# SMT_Nixie_Board_HV5623.net
KiCad netlist of a schematic drawn in EAGLE
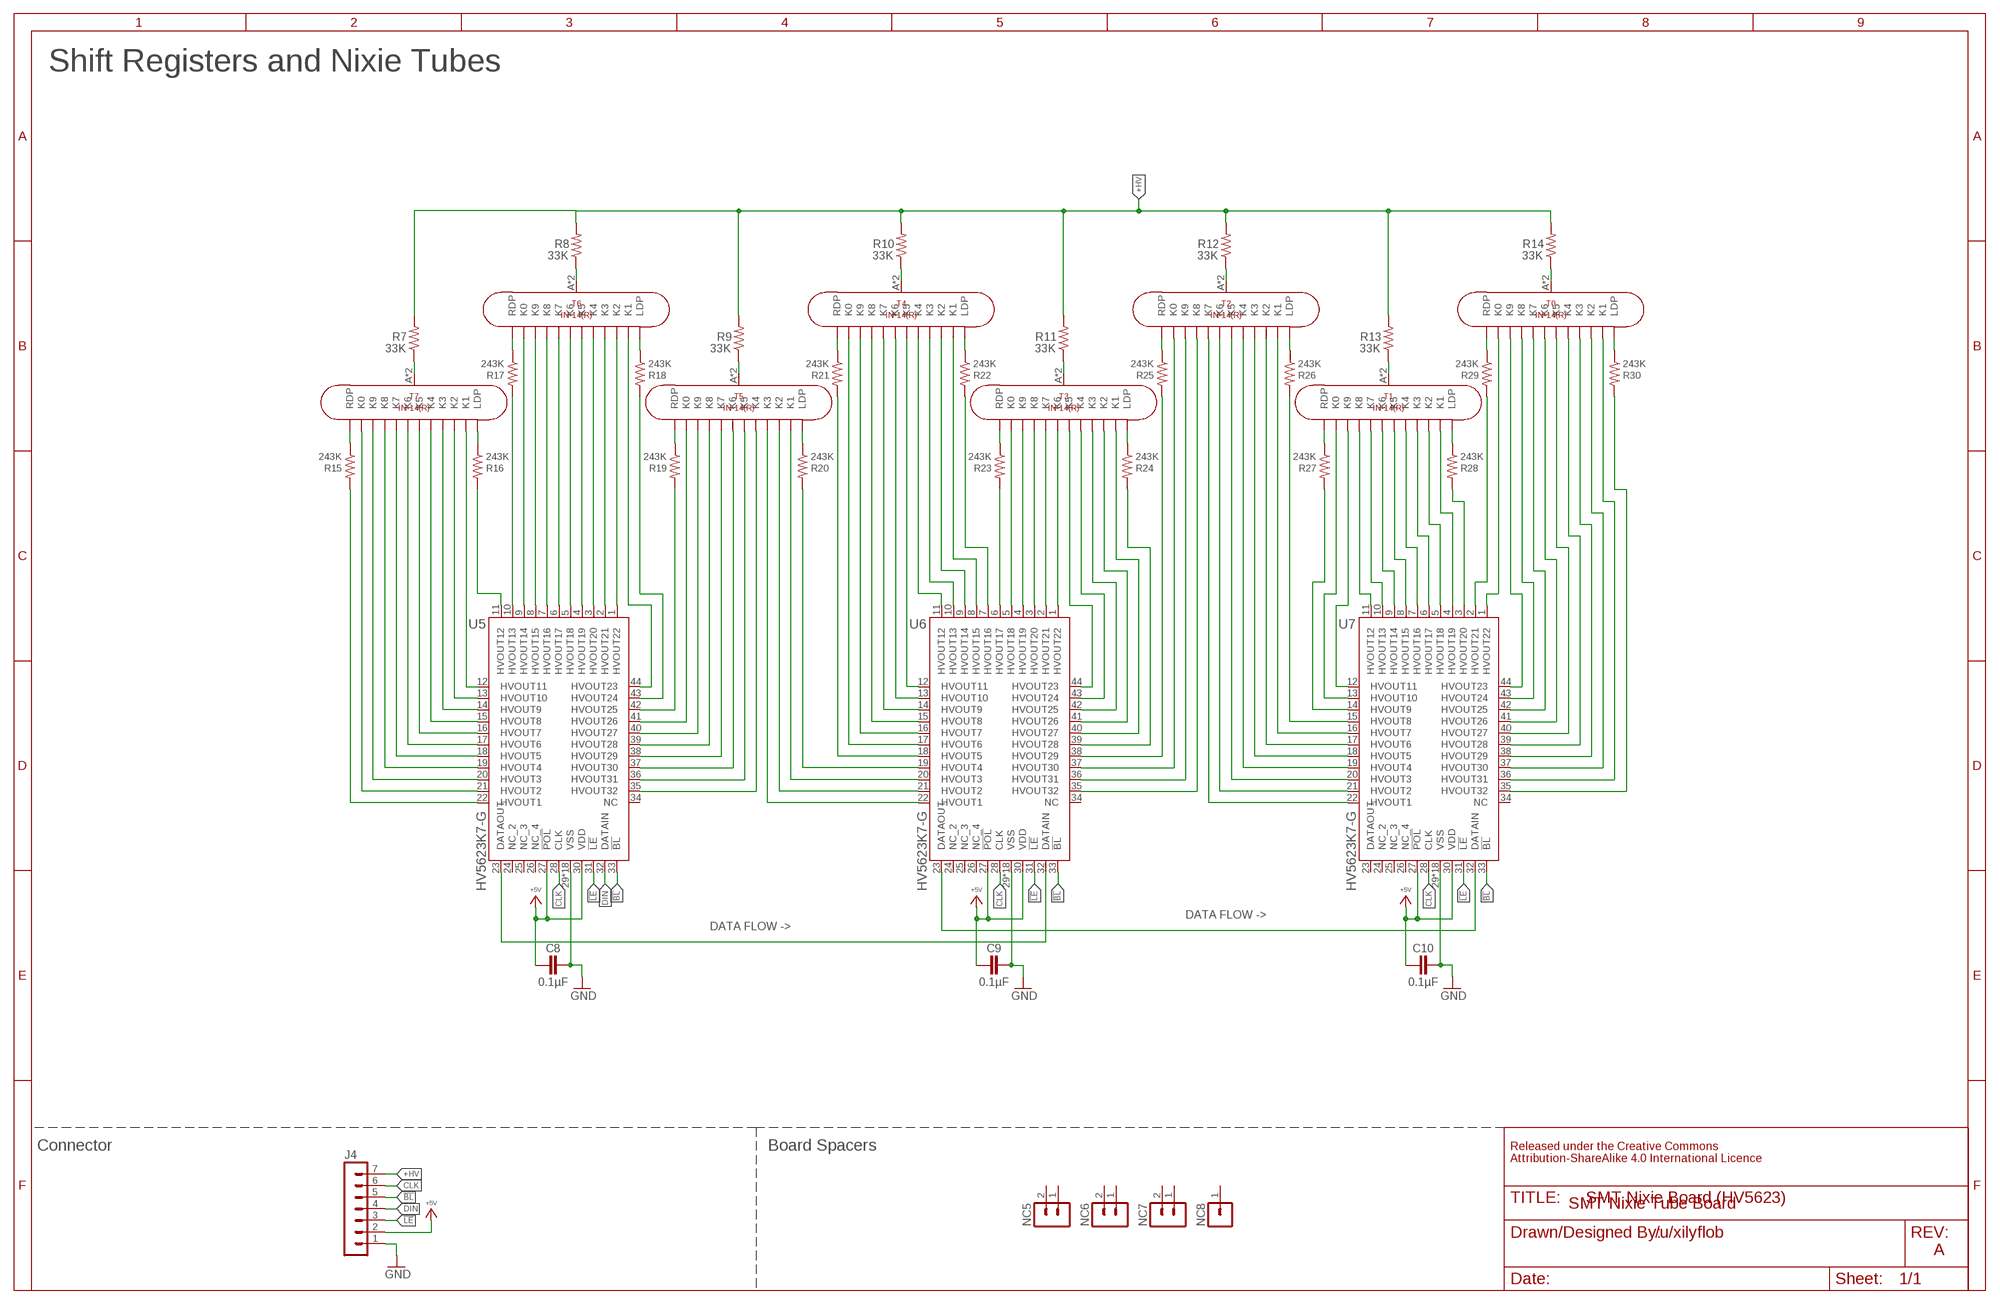
[diagram p0: schematic, sheet 1]

(export (version "E")
  (design (tool "Eeschema 10.0.6"))
  (components
    (comp (ref "C8")
      (value "0.1µF")
      (footprint "eagle-import:C0805")
      (libsource (lib "eagle-import") (part "C-EU"))
    )
    (comp (ref "C9")
      (value "0.1µF")
      (footprint "eagle-import:C0805")
      (libsource (lib "eagle-import") (part "C-EU"))
    )
    (comp (ref "C10")
      (value "0.1µF")
      (footprint "eagle-import:C0805")
      (libsource (lib "eagle-import") (part "C-EU"))
    )
    (comp (ref "J4")
      (value "1")
      (footprint "eagle-import:MA07")
      (libsource (lib "eagle-import") (part "MA07"))
    )
    (comp (ref "NC5")
      (value "MA02")
      (footprint "eagle-import:MA02")
      (libsource (lib "eagle-import") (part "MA02"))
    )
    (comp (ref "NC6")
      (value "MA02")
      (footprint "eagle-import:MA02")
      (libsource (lib "eagle-import") (part "MA02"))
    )
    (comp (ref "NC7")
      (value "MA02")
      (footprint "eagle-import:MA02")
      (libsource (lib "eagle-import") (part "MA02"))
    )
    (comp (ref "NC8")
      (value "MA01")
      (footprint "eagle-import:MA01")
      (libsource (lib "eagle-import") (part "MA01"))
    )
    (comp (ref "R7")
      (value "33K")
      (footprint "eagle-import:R2512")
      (libsource (lib "eagle-import") (part "R-US_R2512"))
    )
    (comp (ref "R8")
      (value "33K")
      (footprint "eagle-import:R2512")
      (libsource (lib "eagle-import") (part "R-US_R2512"))
    )
    (comp (ref "R9")
      (value "33K")
      (footprint "eagle-import:R2512")
      (libsource (lib "eagle-import") (part "R-US_R2512"))
    )
    (comp (ref "R10")
      (value "33K")
      (footprint "eagle-import:R2512")
      (libsource (lib "eagle-import") (part "R-US_R2512"))
    )
    (comp (ref "R11")
      (value "33K")
      (footprint "eagle-import:R2512")
      (libsource (lib "eagle-import") (part "R-US_R2512"))
    )
    (comp (ref "R12")
      (value "33K")
      (footprint "eagle-import:R2512")
      (libsource (lib "eagle-import") (part "R-US_R2512"))
    )
    (comp (ref "R13")
      (value "33K")
      (footprint "eagle-import:R2512")
      (libsource (lib "eagle-import") (part "R-US_R2512"))
    )
    (comp (ref "R14")
      (value "33K")
      (footprint "eagle-import:R2512")
      (libsource (lib "eagle-import") (part "R-US_R2512"))
    )
    (comp (ref "R15")
      (value "243K")
      (footprint "eagle-import:R2010")
      (libsource (lib "eagle-import") (part "R-US_R2010"))
    )
    (comp (ref "R16")
      (value "243K")
      (footprint "eagle-import:R2010")
      (libsource (lib "eagle-import") (part "R-US_R2010"))
    )
    (comp (ref "R17")
      (value "243K")
      (footprint "eagle-import:R2010")
      (libsource (lib "eagle-import") (part "R-US_R2010"))
    )
    (comp (ref "R18")
      (value "243K")
      (footprint "eagle-import:R2010")
      (libsource (lib "eagle-import") (part "R-US_R2010"))
    )
    (comp (ref "R19")
      (value "243K")
      (footprint "eagle-import:R2010")
      (libsource (lib "eagle-import") (part "R-US_R2010"))
    )
    (comp (ref "R20")
      (value "243K")
      (footprint "eagle-import:R2010")
      (libsource (lib "eagle-import") (part "R-US_R2010"))
    )
    (comp (ref "R21")
      (value "243K")
      (footprint "eagle-import:R2010")
      (libsource (lib "eagle-import") (part "R-US_R2010"))
    )
    (comp (ref "R22")
      (value "243K")
      (footprint "eagle-import:R2010")
      (libsource (lib "eagle-import") (part "R-US_R2010"))
    )
    (comp (ref "R23")
      (value "243K")
      (footprint "eagle-import:R2010")
      (libsource (lib "eagle-import") (part "R-US_R2010"))
    )
    (comp (ref "R24")
      (value "243K")
      (footprint "eagle-import:R2010")
      (libsource (lib "eagle-import") (part "R-US_R2010"))
    )
    (comp (ref "R25")
      (value "243K")
      (footprint "eagle-import:R2010")
      (libsource (lib "eagle-import") (part "R-US_R2010"))
    )
    (comp (ref "R26")
      (value "243K")
      (footprint "eagle-import:R2010")
      (libsource (lib "eagle-import") (part "R-US_R2010"))
    )
    (comp (ref "R27")
      (value "243K")
      (footprint "eagle-import:R2010")
      (libsource (lib "eagle-import") (part "R-US_R2010"))
    )
    (comp (ref "R28")
      (value "243K")
      (footprint "eagle-import:R2010")
      (libsource (lib "eagle-import") (part "R-US_R2010"))
    )
    (comp (ref "R29")
      (value "243K")
      (footprint "eagle-import:R2010")
      (libsource (lib "eagle-import") (part "R-US_R2010"))
    )
    (comp (ref "R30")
      (value "243K")
      (footprint "eagle-import:R2010")
      (libsource (lib "eagle-import") (part "R-US_R2010"))
    )
    (comp (ref "T0")
      (value "IN-14(R)")
      (footprint "eagle-import:IN-14_REVERSE")
      (libsource (lib "eagle-import") (part "IN-14(R)"))
    )
    (comp (ref "T1")
      (value "IN-14(R)")
      (footprint "eagle-import:IN-14_REVERSE")
      (libsource (lib "eagle-import") (part "IN-14(R)"))
    )
    (comp (ref "T2")
      (value "IN-14(R)")
      (footprint "eagle-import:IN-14_REVERSE")
      (libsource (lib "eagle-import") (part "IN-14(R)"))
    )
    (comp (ref "T3")
      (value "IN-14(R)")
      (footprint "eagle-import:IN-14_REVERSE")
      (libsource (lib "eagle-import") (part "IN-14(R)"))
    )
    (comp (ref "T4")
      (value "IN-14(R)")
      (footprint "eagle-import:IN-14_REVERSE")
      (libsource (lib "eagle-import") (part "IN-14(R)"))
    )
    (comp (ref "T5")
      (value "IN-14(R)")
      (footprint "eagle-import:IN-14_REVERSE")
      (libsource (lib "eagle-import") (part "IN-14(R)"))
    )
    (comp (ref "T6")
      (value "IN-14(R)")
      (footprint "eagle-import:IN-14_REVERSE")
      (libsource (lib "eagle-import") (part "IN-14(R)"))
    )
    (comp (ref "T7")
      (value "IN-14(R)")
      (footprint "eagle-import:IN-14_REVERSE")
      (libsource (lib "eagle-import") (part "IN-14(R)"))
    )
    (comp (ref "U5")
      (value "HV5623K7-G")
      (footprint "eagle-import:WQFN-44")
      (libsource (lib "eagle-import") (part "HV5623K7-G"))
    )
    (comp (ref "U6")
      (value "HV5623K7-G")
      (footprint "eagle-import:WQFN-44")
      (libsource (lib "eagle-import") (part "HV5623K7-G"))
    )
    (comp (ref "U7")
      (value "HV5623K7-G")
      (footprint "eagle-import:WQFN-44")
      (libsource (lib "eagle-import") (part "HV5623K7-G"))
    )
  )
  (nets
    (net (code "1") (name "+5V") (class "Default")
      (node (ref "C10") (pin "1") (pinfunction "1_1") (pintype "passive"))
      (node (ref "C8") (pin "1") (pinfunction "1_1") (pintype "passive"))
      (node (ref "C9") (pin "1") (pinfunction "1_1") (pintype "passive"))
      (node (ref "J4") (pin "2") (pinfunction "2_2") (pintype "passive"))
      (node (ref "U5") (pin "27") (pinfunction "~{POL}_27") (pintype "passive"))
      (node (ref "U5") (pin "30") (pinfunction "VDD_30") (pintype "power_in"))
      (node (ref "U6") (pin "27") (pinfunction "~{POL}_27") (pintype "passive"))
      (node (ref "U6") (pin "30") (pinfunction "VDD_30") (pintype "power_in"))
      (node (ref "U7") (pin "27") (pinfunction "~{POL}_27") (pintype "passive"))
      (node (ref "U7") (pin "30") (pinfunction "VDD_30") (pintype "power_in"))
    )
    (net (code "2") (name "+HV") (class "Default")
      (node (ref "J4") (pin "7") (pinfunction "7_7") (pintype "passive"))
      (node (ref "R10") (pin "2") (pinfunction "2_2") (pintype "passive"))
      (node (ref "R11") (pin "2") (pinfunction "2_2") (pintype "passive"))
      (node (ref "R12") (pin "2") (pinfunction "2_2") (pintype "passive"))
      (node (ref "R13") (pin "2") (pinfunction "2_2") (pintype "passive"))
      (node (ref "R14") (pin "2") (pinfunction "2_2") (pintype "passive"))
      (node (ref "R7") (pin "2") (pinfunction "2_2") (pintype "passive"))
      (node (ref "R8") (pin "2") (pinfunction "2_2") (pintype "passive"))
      (node (ref "R9") (pin "2") (pinfunction "2_2") (pintype "passive"))
    )
    (net (code "3") (name "/~{BL}") (class "Default")
      (node (ref "J4") (pin "5") (pinfunction "5_5") (pintype "passive"))
      (node (ref "U5") (pin "33") (pinfunction "~{BL}_33") (pintype "passive"))
      (node (ref "U6") (pin "33") (pinfunction "~{BL}_33") (pintype "passive"))
      (node (ref "U7") (pin "33") (pinfunction "~{BL}_33") (pintype "passive"))
    )
    (net (code "4") (name "/~{LE}") (class "Default")
      (node (ref "J4") (pin "3") (pinfunction "3_3") (pintype "passive"))
      (node (ref "U5") (pin "31") (pinfunction "~{LE}_31") (pintype "input"))
      (node (ref "U6") (pin "31") (pinfunction "~{LE}_31") (pintype "input"))
      (node (ref "U7") (pin "31") (pinfunction "~{LE}_31") (pintype "input"))
    )
    (net (code "5") (name "CLK") (class "Default")
      (node (ref "J4") (pin "6") (pinfunction "6_6") (pintype "passive"))
      (node (ref "U5") (pin "28") (pinfunction "CLK_28") (pintype "input"))
      (node (ref "U6") (pin "28") (pinfunction "CLK_28") (pintype "input"))
      (node (ref "U7") (pin "28") (pinfunction "CLK_28") (pintype "input"))
    )
    (net (code "6") (name "DIN") (class "Default")
      (node (ref "J4") (pin "4") (pinfunction "4_4") (pintype "passive"))
      (node (ref "U5") (pin "32") (pinfunction "DATAIN_32") (pintype "input"))
    )
    (net (code "7") (name "GND") (class "Default")
      (node (ref "C10") (pin "2") (pinfunction "2_2") (pintype "passive"))
      (node (ref "C8") (pin "2") (pinfunction "2_2") (pintype "passive"))
      (node (ref "C9") (pin "2") (pinfunction "2_2") (pintype "passive"))
      (node (ref "J4") (pin "1") (pinfunction "1_1") (pintype "passive"))
      (node (ref "U5") (pin "29") (pinfunction "VSS_29") (pintype "power_in"))
      (node (ref "U5") (pin "P$1") (pinfunction "VSS_P$1") (pintype "power_in"))
      (node (ref "U5") (pin "P$10") (pinfunction "VSS_P$10") (pintype "power_in"))
      (node (ref "U5") (pin "P$11") (pinfunction "VSS_P$11") (pintype "power_in"))
      (node (ref "U5") (pin "P$12") (pinfunction "VSS_P$12") (pintype "power_in"))
      (node (ref "U5") (pin "P$13") (pinfunction "VSS_P$13") (pintype "power_in"))
      (node (ref "U5") (pin "P$14") (pinfunction "VSS_P$14") (pintype "power_in"))
      (node (ref "U5") (pin "P$15") (pinfunction "VSS_P$15") (pintype "power_in"))
      (node (ref "U5") (pin "P$16") (pinfunction "VSS_P$16") (pintype "power_in"))
      (node (ref "U5") (pin "P$2") (pinfunction "VSS_P$2") (pintype "power_in"))
      (node (ref "U5") (pin "P$3") (pinfunction "VSS_P$3") (pintype "power_in"))
      (node (ref "U5") (pin "P$4") (pinfunction "VSS_P$4") (pintype "power_in"))
      (node (ref "U5") (pin "P$5") (pinfunction "VSS_P$5") (pintype "power_in"))
      (node (ref "U5") (pin "P$6") (pinfunction "VSS_P$6") (pintype "power_in"))
      (node (ref "U5") (pin "P$7") (pinfunction "VSS_P$7") (pintype "power_in"))
      (node (ref "U5") (pin "P$8") (pinfunction "VSS_P$8") (pintype "power_in"))
      (node (ref "U5") (pin "P$9") (pinfunction "VSS_P$9") (pintype "power_in"))
      (node (ref "U5") (pin "TP") (pinfunction "VSS_TP") (pintype "power_in"))
      (node (ref "U6") (pin "29") (pinfunction "VSS_29") (pintype "power_in"))
      (node (ref "U6") (pin "P$1") (pinfunction "VSS_P$1") (pintype "power_in"))
      (node (ref "U6") (pin "P$10") (pinfunction "VSS_P$10") (pintype "power_in"))
      (node (ref "U6") (pin "P$11") (pinfunction "VSS_P$11") (pintype "power_in"))
      (node (ref "U6") (pin "P$12") (pinfunction "VSS_P$12") (pintype "power_in"))
      (node (ref "U6") (pin "P$13") (pinfunction "VSS_P$13") (pintype "power_in"))
      (node (ref "U6") (pin "P$14") (pinfunction "VSS_P$14") (pintype "power_in"))
      (node (ref "U6") (pin "P$15") (pinfunction "VSS_P$15") (pintype "power_in"))
      (node (ref "U6") (pin "P$16") (pinfunction "VSS_P$16") (pintype "power_in"))
      (node (ref "U6") (pin "P$2") (pinfunction "VSS_P$2") (pintype "power_in"))
      (node (ref "U6") (pin "P$3") (pinfunction "VSS_P$3") (pintype "power_in"))
      (node (ref "U6") (pin "P$4") (pinfunction "VSS_P$4") (pintype "power_in"))
      (node (ref "U6") (pin "P$5") (pinfunction "VSS_P$5") (pintype "power_in"))
      (node (ref "U6") (pin "P$6") (pinfunction "VSS_P$6") (pintype "power_in"))
      (node (ref "U6") (pin "P$7") (pinfunction "VSS_P$7") (pintype "power_in"))
      (node (ref "U6") (pin "P$8") (pinfunction "VSS_P$8") (pintype "power_in"))
      (node (ref "U6") (pin "P$9") (pinfunction "VSS_P$9") (pintype "power_in"))
      (node (ref "U6") (pin "TP") (pinfunction "VSS_TP") (pintype "power_in"))
      (node (ref "U7") (pin "29") (pinfunction "VSS_29") (pintype "power_in"))
      (node (ref "U7") (pin "P$1") (pinfunction "VSS_P$1") (pintype "power_in"))
      (node (ref "U7") (pin "P$10") (pinfunction "VSS_P$10") (pintype "power_in"))
      (node (ref "U7") (pin "P$11") (pinfunction "VSS_P$11") (pintype "power_in"))
      (node (ref "U7") (pin "P$12") (pinfunction "VSS_P$12") (pintype "power_in"))
      (node (ref "U7") (pin "P$13") (pinfunction "VSS_P$13") (pintype "power_in"))
      (node (ref "U7") (pin "P$14") (pinfunction "VSS_P$14") (pintype "power_in"))
      (node (ref "U7") (pin "P$15") (pinfunction "VSS_P$15") (pintype "power_in"))
      (node (ref "U7") (pin "P$16") (pinfunction "VSS_P$16") (pintype "power_in"))
      (node (ref "U7") (pin "P$2") (pinfunction "VSS_P$2") (pintype "power_in"))
      (node (ref "U7") (pin "P$3") (pinfunction "VSS_P$3") (pintype "power_in"))
      (node (ref "U7") (pin "P$4") (pinfunction "VSS_P$4") (pintype "power_in"))
      (node (ref "U7") (pin "P$5") (pinfunction "VSS_P$5") (pintype "power_in"))
      (node (ref "U7") (pin "P$6") (pinfunction "VSS_P$6") (pintype "power_in"))
      (node (ref "U7") (pin "P$7") (pinfunction "VSS_P$7") (pintype "power_in"))
      (node (ref "U7") (pin "P$8") (pinfunction "VSS_P$8") (pintype "power_in"))
      (node (ref "U7") (pin "P$9") (pinfunction "VSS_P$9") (pintype "power_in"))
      (node (ref "U7") (pin "TP") (pinfunction "VSS_TP") (pintype "power_in"))
    )
    (net (code "8") (name "Net-(R7-Pad1)") (class "Default")
      (node (ref "R7") (pin "1") (pinfunction "1_1") (pintype "passive"))
      (node (ref "T7") (pin "A") (pinfunction "A_A") (pintype "output"))
      (node (ref "T7") (pin "A_1") (pinfunction "A_A_1") (pintype "output"))
    )
    (net (code "9") (name "Net-(R8-Pad1)") (class "Default")
      (node (ref "R8") (pin "1") (pinfunction "1_1") (pintype "passive"))
      (node (ref "T6") (pin "A") (pinfunction "A_A") (pintype "output"))
      (node (ref "T6") (pin "A_1") (pinfunction "A_A_1") (pintype "output"))
    )
    (net (code "10") (name "Net-(R9-Pad1)") (class "Default")
      (node (ref "R9") (pin "1") (pinfunction "1_1") (pintype "passive"))
      (node (ref "T5") (pin "A") (pinfunction "A_A") (pintype "output"))
      (node (ref "T5") (pin "A_1") (pinfunction "A_A_1") (pintype "output"))
    )
    (net (code "11") (name "Net-(R10-Pad1)") (class "Default")
      (node (ref "R10") (pin "1") (pinfunction "1_1") (pintype "passive"))
      (node (ref "T4") (pin "A") (pinfunction "A_A") (pintype "output"))
      (node (ref "T4") (pin "A_1") (pinfunction "A_A_1") (pintype "output"))
    )
    (net (code "12") (name "Net-(R11-Pad1)") (class "Default")
      (node (ref "R11") (pin "1") (pinfunction "1_1") (pintype "passive"))
      (node (ref "T3") (pin "A") (pinfunction "A_A") (pintype "output"))
      (node (ref "T3") (pin "A_1") (pinfunction "A_A_1") (pintype "output"))
    )
    (net (code "13") (name "Net-(R12-Pad1)") (class "Default")
      (node (ref "R12") (pin "1") (pinfunction "1_1") (pintype "passive"))
      (node (ref "T2") (pin "A") (pinfunction "A_A") (pintype "output"))
      (node (ref "T2") (pin "A_1") (pinfunction "A_A_1") (pintype "output"))
    )
    (net (code "14") (name "Net-(R13-Pad1)") (class "Default")
      (node (ref "R13") (pin "1") (pinfunction "1_1") (pintype "passive"))
      (node (ref "T1") (pin "A") (pinfunction "A_A") (pintype "output"))
      (node (ref "T1") (pin "A_1") (pinfunction "A_A_1") (pintype "output"))
    )
    (net (code "15") (name "Net-(R14-Pad1)") (class "Default")
      (node (ref "R14") (pin "1") (pinfunction "1_1") (pintype "passive"))
      (node (ref "T0") (pin "A") (pinfunction "A_A") (pintype "output"))
      (node (ref "T0") (pin "A_1") (pinfunction "A_A_1") (pintype "output"))
    )
    (net (code "16") (name "Net-(R15-Pad1)") (class "Default")
      (node (ref "R15") (pin "1") (pinfunction "1_1") (pintype "passive"))
      (node (ref "T7") (pin "RDP") (pinfunction "RDP_RDP") (pintype "input"))
      (node (ref "T7") (pin "RDP_1") (pinfunction "RDP_RDP_1") (pintype "input"))
    )
    (net (code "17") (name "Net-(R16-Pad1)") (class "Default")
      (node (ref "R16") (pin "1") (pinfunction "1_1") (pintype "passive"))
      (node (ref "T7") (pin "LDP") (pinfunction "LDP_LDP") (pintype "input"))
      (node (ref "T7") (pin "LDP_1") (pinfunction "LDP_LDP_1") (pintype "input"))
    )
    (net (code "18") (name "Net-(R17-Pad1)") (class "Default")
      (node (ref "R17") (pin "1") (pinfunction "1_1") (pintype "passive"))
      (node (ref "T6") (pin "RDP") (pinfunction "RDP_RDP") (pintype "input"))
      (node (ref "T6") (pin "RDP_1") (pinfunction "RDP_RDP_1") (pintype "input"))
    )
    (net (code "19") (name "Net-(R18-Pad1)") (class "Default")
      (node (ref "R18") (pin "1") (pinfunction "1_1") (pintype "passive"))
      (node (ref "T6") (pin "LDP") (pinfunction "LDP_LDP") (pintype "input"))
      (node (ref "T6") (pin "LDP_1") (pinfunction "LDP_LDP_1") (pintype "input"))
    )
    (net (code "20") (name "Net-(R19-Pad1)") (class "Default")
      (node (ref "R19") (pin "1") (pinfunction "1_1") (pintype "passive"))
      (node (ref "T5") (pin "RDP") (pinfunction "RDP_RDP") (pintype "input"))
      (node (ref "T5") (pin "RDP_1") (pinfunction "RDP_RDP_1") (pintype "input"))
    )
    (net (code "21") (name "Net-(R20-Pad1)") (class "Default")
      (node (ref "R20") (pin "1") (pinfunction "1_1") (pintype "passive"))
      (node (ref "T5") (pin "LDP") (pinfunction "LDP_LDP") (pintype "input"))
      (node (ref "T5") (pin "LDP_1") (pinfunction "LDP_LDP_1") (pintype "input"))
    )
    (net (code "22") (name "Net-(R21-Pad1)") (class "Default")
      (node (ref "R21") (pin "1") (pinfunction "1_1") (pintype "passive"))
      (node (ref "T4") (pin "RDP") (pinfunction "RDP_RDP") (pintype "input"))
      (node (ref "T4") (pin "RDP_1") (pinfunction "RDP_RDP_1") (pintype "input"))
    )
    (net (code "23") (name "Net-(R22-Pad1)") (class "Default")
      (node (ref "R22") (pin "1") (pinfunction "1_1") (pintype "passive"))
      (node (ref "T4") (pin "LDP") (pinfunction "LDP_LDP") (pintype "input"))
      (node (ref "T4") (pin "LDP_1") (pinfunction "LDP_LDP_1") (pintype "input"))
    )
    (net (code "24") (name "Net-(R23-Pad1)") (class "Default")
      (node (ref "R23") (pin "1") (pinfunction "1_1") (pintype "passive"))
      (node (ref "T3") (pin "RDP") (pinfunction "RDP_RDP") (pintype "input"))
      (node (ref "T3") (pin "RDP_1") (pinfunction "RDP_RDP_1") (pintype "input"))
    )
    (net (code "25") (name "Net-(R24-Pad1)") (class "Default")
      (node (ref "R24") (pin "1") (pinfunction "1_1") (pintype "passive"))
      (node (ref "T3") (pin "LDP") (pinfunction "LDP_LDP") (pintype "input"))
      (node (ref "T3") (pin "LDP_1") (pinfunction "LDP_LDP_1") (pintype "input"))
    )
    (net (code "26") (name "Net-(R25-Pad1)") (class "Default")
      (node (ref "R25") (pin "1") (pinfunction "1_1") (pintype "passive"))
      (node (ref "T2") (pin "RDP") (pinfunction "RDP_RDP") (pintype "input"))
      (node (ref "T2") (pin "RDP_1") (pinfunction "RDP_RDP_1") (pintype "input"))
    )
    (net (code "27") (name "Net-(R26-Pad1)") (class "Default")
      (node (ref "R26") (pin "1") (pinfunction "1_1") (pintype "passive"))
      (node (ref "T2") (pin "LDP") (pinfunction "LDP_LDP") (pintype "input"))
      (node (ref "T2") (pin "LDP_1") (pinfunction "LDP_LDP_1") (pintype "input"))
    )
    (net (code "28") (name "Net-(R27-Pad1)") (class "Default")
      (node (ref "R27") (pin "1") (pinfunction "1_1") (pintype "passive"))
      (node (ref "T1") (pin "RDP") (pinfunction "RDP_RDP") (pintype "input"))
      (node (ref "T1") (pin "RDP_1") (pinfunction "RDP_RDP_1") (pintype "input"))
    )
    (net (code "29") (name "Net-(R28-Pad1)") (class "Default")
      (node (ref "R28") (pin "1") (pinfunction "1_1") (pintype "passive"))
      (node (ref "T1") (pin "LDP") (pinfunction "LDP_LDP") (pintype "input"))
      (node (ref "T1") (pin "LDP_1") (pinfunction "LDP_LDP_1") (pintype "input"))
    )
    (net (code "30") (name "Net-(R29-Pad1)") (class "Default")
      (node (ref "R29") (pin "1") (pinfunction "1_1") (pintype "passive"))
      (node (ref "T0") (pin "RDP") (pinfunction "RDP_RDP") (pintype "input"))
      (node (ref "T0") (pin "RDP_1") (pinfunction "RDP_RDP_1") (pintype "input"))
    )
    (net (code "31") (name "Net-(R30-Pad1)") (class "Default")
      (node (ref "R30") (pin "1") (pinfunction "1_1") (pintype "passive"))
      (node (ref "T0") (pin "LDP") (pinfunction "LDP_LDP") (pintype "input"))
      (node (ref "T0") (pin "LDP_1") (pinfunction "LDP_LDP_1") (pintype "input"))
    )
    (net (code "32") (name "Net-(U5-DATAOUT)") (class "Default")
      (node (ref "U5") (pin "23") (pinfunction "DATAOUT_23") (pintype "output"))
      (node (ref "U6") (pin "32") (pinfunction "DATAIN_32") (pintype "input"))
    )
    (net (code "33") (name "Net-(U5-HVOUT1)") (class "Default")
      (node (ref "R15") (pin "2") (pinfunction "2_2") (pintype "passive"))
      (node (ref "U5") (pin "22") (pinfunction "HVOUT1_22") (pintype "output"))
    )
    (net (code "34") (name "Net-(U5-HVOUT2)") (class "Default")
      (node (ref "T7") (pin "K0") (pinfunction "K0_K0") (pintype "input"))
      (node (ref "T7") (pin "K0_1") (pinfunction "K0_K0_1") (pintype "input"))
      (node (ref "U5") (pin "21") (pinfunction "HVOUT2_21") (pintype "output"))
    )
    (net (code "35") (name "Net-(U5-HVOUT3)") (class "Default")
      (node (ref "T7") (pin "K9") (pinfunction "K9_K9") (pintype "input"))
      (node (ref "T7") (pin "K9_1") (pinfunction "K9_K9_1") (pintype "input"))
      (node (ref "U5") (pin "20") (pinfunction "HVOUT3_20") (pintype "output"))
    )
    (net (code "36") (name "Net-(U5-HVOUT4)") (class "Default")
      (node (ref "T7") (pin "K8") (pinfunction "K8_K8") (pintype "input"))
      (node (ref "T7") (pin "K8_1") (pinfunction "K8_K8_1") (pintype "input"))
      (node (ref "U5") (pin "19") (pinfunction "HVOUT4_19") (pintype "output"))
    )
    (net (code "37") (name "Net-(U5-HVOUT5)") (class "Default")
      (node (ref "T7") (pin "K7") (pinfunction "K7_K7") (pintype "input"))
      (node (ref "T7") (pin "K7_1") (pinfunction "K7_K7_1") (pintype "input"))
      (node (ref "U5") (pin "18") (pinfunction "HVOUT5_18") (pintype "output"))
    )
    (net (code "38") (name "Net-(U5-HVOUT6)") (class "Default")
      (node (ref "T7") (pin "K6") (pinfunction "K6_K6") (pintype "input"))
      (node (ref "T7") (pin "K6_1") (pinfunction "K6_K6_1") (pintype "input"))
      (node (ref "U5") (pin "17") (pinfunction "HVOUT6_17") (pintype "output"))
    )
    (net (code "39") (name "Net-(U5-HVOUT7)") (class "Default")
      (node (ref "T7") (pin "K5") (pinfunction "K5_K5") (pintype "input"))
      (node (ref "T7") (pin "K5_1") (pinfunction "K5_K5_1") (pintype "input"))
      (node (ref "U5") (pin "16") (pinfunction "HVOUT7_16") (pintype "output"))
    )
    (net (code "40") (name "Net-(U5-HVOUT8)") (class "Default")
      (node (ref "T7") (pin "K4") (pinfunction "K4_K4") (pintype "input"))
      (node (ref "T7") (pin "K4_1") (pinfunction "K4_K4_1") (pintype "input"))
      (node (ref "U5") (pin "15") (pinfunction "HVOUT8_15") (pintype "output"))
    )
    (net (code "41") (name "Net-(U5-HVOUT9)") (class "Default")
      (node (ref "T7") (pin "K3") (pinfunction "K3_K3") (pintype "input"))
      (node (ref "T7") (pin "K3_1") (pinfunction "K3_K3_1") (pintype "input"))
      (node (ref "U5") (pin "14") (pinfunction "HVOUT9_14") (pintype "output"))
    )
    (net (code "42") (name "Net-(U5-HVOUT10)") (class "Default")
      (node (ref "T7") (pin "K2") (pinfunction "K2_K2") (pintype "input"))
      (node (ref "T7") (pin "K2_1") (pinfunction "K2_K2_1") (pintype "input"))
      (node (ref "U5") (pin "13") (pinfunction "HVOUT10_13") (pintype "output"))
    )
    (net (code "43") (name "Net-(U5-HVOUT11)") (class "Default")
      (node (ref "T7") (pin "K1") (pinfunction "K1_K1") (pintype "input"))
      (node (ref "T7") (pin "K1_1") (pinfunction "K1_K1_1") (pintype "input"))
      (node (ref "U5") (pin "12") (pinfunction "HVOUT11_12") (pintype "output"))
    )
    (net (code "44") (name "Net-(U5-HVOUT12)") (class "Default")
      (node (ref "R16") (pin "2") (pinfunction "2_2") (pintype "passive"))
      (node (ref "U5") (pin "11") (pinfunction "HVOUT12_11") (pintype "output"))
    )
    (net (code "45") (name "Net-(U5-HVOUT13)") (class "Default")
      (node (ref "R17") (pin "2") (pinfunction "2_2") (pintype "passive"))
      (node (ref "U5") (pin "10") (pinfunction "HVOUT13_10") (pintype "output"))
    )
    (net (code "46") (name "Net-(U5-HVOUT14)") (class "Default")
      (node (ref "T6") (pin "K0") (pinfunction "K0_K0") (pintype "input"))
      (node (ref "T6") (pin "K0_1") (pinfunction "K0_K0_1") (pintype "input"))
      (node (ref "U5") (pin "9") (pinfunction "HVOUT14_9") (pintype "output"))
    )
    (net (code "47") (name "Net-(U5-HVOUT15)") (class "Default")
      (node (ref "T6") (pin "K9") (pinfunction "K9_K9") (pintype "input"))
      (node (ref "T6") (pin "K9_1") (pinfunction "K9_K9_1") (pintype "input"))
      (node (ref "U5") (pin "8") (pinfunction "HVOUT15_8") (pintype "output"))
    )
    (net (code "48") (name "Net-(U5-HVOUT16)") (class "Default")
      (node (ref "T6") (pin "K8") (pinfunction "K8_K8") (pintype "input"))
      (node (ref "T6") (pin "K8_1") (pinfunction "K8_K8_1") (pintype "input"))
      (node (ref "U5") (pin "7") (pinfunction "HVOUT16_7") (pintype "output"))
    )
    (net (code "49") (name "Net-(U5-HVOUT17)") (class "Default")
      (node (ref "T6") (pin "K7") (pinfunction "K7_K7") (pintype "input"))
      (node (ref "T6") (pin "K7_1") (pinfunction "K7_K7_1") (pintype "input"))
      (node (ref "U5") (pin "6") (pinfunction "HVOUT17_6") (pintype "output"))
    )
    (net (code "50") (name "Net-(U5-HVOUT18)") (class "Default")
      (node (ref "T6") (pin "K6") (pinfunction "K6_K6") (pintype "input"))
      (node (ref "T6") (pin "K6_1") (pinfunction "K6_K6_1") (pintype "input"))
      (node (ref "U5") (pin "5") (pinfunction "HVOUT18_5") (pintype "output"))
    )
    (net (code "51") (name "Net-(U5-HVOUT19)") (class "Default")
      (node (ref "T6") (pin "K5") (pinfunction "K5_K5") (pintype "input"))
      (node (ref "T6") (pin "K5_1") (pinfunction "K5_K5_1") (pintype "input"))
      (node (ref "U5") (pin "4") (pinfunction "HVOUT19_4") (pintype "output"))
    )
    (net (code "52") (name "Net-(U5-HVOUT20)") (class "Default")
      (node (ref "T6") (pin "K4") (pinfunction "K4_K4") (pintype "input"))
      (node (ref "T6") (pin "K4_1") (pinfunction "K4_K4_1") (pintype "input"))
      (node (ref "U5") (pin "3") (pinfunction "HVOUT20_3") (pintype "output"))
    )
    (net (code "53") (name "Net-(U5-HVOUT21)") (class "Default")
      (node (ref "T6") (pin "K3") (pinfunction "K3_K3") (pintype "input"))
      (node (ref "T6") (pin "K3_1") (pinfunction "K3_K3_1") (pintype "input"))
      (node (ref "U5") (pin "2") (pinfunction "HVOUT21_2") (pintype "output"))
    )
    (net (code "54") (name "Net-(U5-HVOUT22)") (class "Default")
      (node (ref "T6") (pin "K2") (pinfunction "K2_K2") (pintype "input"))
      (node (ref "T6") (pin "K2_1") (pinfunction "K2_K2_1") (pintype "input"))
      (node (ref "U5") (pin "1") (pinfunction "HVOUT22_1") (pintype "output"))
    )
    (net (code "55") (name "Net-(U5-HVOUT23)") (class "Default")
      (node (ref "T6") (pin "K1") (pinfunction "K1_K1") (pintype "input"))
      (node (ref "T6") (pin "K1_1") (pinfunction "K1_K1_1") (pintype "input"))
      (node (ref "U5") (pin "44") (pinfunction "HVOUT23_44") (pintype "output"))
    )
    (net (code "56") (name "Net-(U5-HVOUT24)") (class "Default")
      (node (ref "R18") (pin "2") (pinfunction "2_2") (pintype "passive"))
      (node (ref "U5") (pin "43") (pinfunction "HVOUT24_43") (pintype "output"))
    )
    (net (code "57") (name "Net-(U5-HVOUT25)") (class "Default")
      (node (ref "R19") (pin "2") (pinfunction "2_2") (pintype "passive"))
      (node (ref "U5") (pin "42") (pinfunction "HVOUT25_42") (pintype "output"))
    )
    (net (code "58") (name "Net-(U5-HVOUT26)") (class "Default")
      (node (ref "T5") (pin "K0") (pinfunction "K0_K0") (pintype "input"))
      (node (ref "T5") (pin "K0_1") (pinfunction "K0_K0_1") (pintype "input"))
      (node (ref "U5") (pin "41") (pinfunction "HVOUT26_41") (pintype "output"))
    )
    (net (code "59") (name "Net-(U5-HVOUT27)") (class "Default")
      (node (ref "T5") (pin "K9") (pinfunction "K9_K9") (pintype "input"))
      (node (ref "T5") (pin "K9_1") (pinfunction "K9_K9_1") (pintype "input"))
      (node (ref "U5") (pin "40") (pinfunction "HVOUT27_40") (pintype "output"))
    )
    (net (code "60") (name "Net-(U5-HVOUT28)") (class "Default")
      (node (ref "T5") (pin "K8") (pinfunction "K8_K8") (pintype "input"))
      (node (ref "T5") (pin "K8_1") (pinfunction "K8_K8_1") (pintype "input"))
      (node (ref "U5") (pin "39") (pinfunction "HVOUT28_39") (pintype "output"))
    )
    (net (code "61") (name "Net-(U5-HVOUT29)") (class "Default")
      (node (ref "T5") (pin "K7") (pinfunction "K7_K7") (pintype "input"))
      (node (ref "T5") (pin "K7_1") (pinfunction "K7_K7_1") (pintype "input"))
      (node (ref "U5") (pin "38") (pinfunction "HVOUT29_38") (pintype "output"))
    )
    (net (code "62") (name "Net-(U5-HVOUT30)") (class "Default")
      (node (ref "T5") (pin "K6") (pinfunction "K6_K6") (pintype "input"))
      (node (ref "T5") (pin "K6_1") (pinfunction "K6_K6_1") (pintype "input"))
      (node (ref "U5") (pin "37") (pinfunction "HVOUT30_37") (pintype "output"))
    )
    (net (code "63") (name "Net-(U5-HVOUT31)") (class "Default")
      (node (ref "T5") (pin "K5") (pinfunction "K5_K5") (pintype "input"))
      (node (ref "T5") (pin "K5_1") (pinfunction "K5_K5_1") (pintype "input"))
      (node (ref "U5") (pin "36") (pinfunction "HVOUT31_36") (pintype "output"))
    )
    (net (code "64") (name "Net-(U5-HVOUT32)") (class "Default")
      (node (ref "T5") (pin "K4") (pinfunction "K4_K4") (pintype "input"))
      (node (ref "T5") (pin "K4_1") (pinfunction "K4_K4_1") (pintype "input"))
      (node (ref "U5") (pin "35") (pinfunction "HVOUT32_35") (pintype "output"))
    )
    (net (code "65") (name "Net-(U6-DATAOUT)") (class "Default")
      (node (ref "U6") (pin "23") (pinfunction "DATAOUT_23") (pintype "output"))
      (node (ref "U7") (pin "32") (pinfunction "DATAIN_32") (pintype "input"))
    )
    (net (code "66") (name "Net-(U6-HVOUT1)") (class "Default")
      (node (ref "T5") (pin "K3") (pinfunction "K3_K3") (pintype "input"))
      (node (ref "T5") (pin "K3_1") (pinfunction "K3_K3_1") (pintype "input"))
      (node (ref "U6") (pin "22") (pinfunction "HVOUT1_22") (pintype "output"))
    )
    (net (code "67") (name "Net-(U6-HVOUT2)") (class "Default")
      (node (ref "T5") (pin "K2") (pinfunction "K2_K2") (pintype "input"))
      (node (ref "T5") (pin "K2_1") (pinfunction "K2_K2_1") (pintype "input"))
      (node (ref "U6") (pin "21") (pinfunction "HVOUT2_21") (pintype "output"))
    )
    (net (code "68") (name "Net-(U6-HVOUT3)") (class "Default")
      (node (ref "T5") (pin "K1") (pinfunction "K1_K1") (pintype "input"))
      (node (ref "T5") (pin "K1_1") (pinfunction "K1_K1_1") (pintype "input"))
      (node (ref "U6") (pin "20") (pinfunction "HVOUT3_20") (pintype "output"))
    )
    (net (code "69") (name "Net-(U6-HVOUT4)") (class "Default")
      (node (ref "R20") (pin "2") (pinfunction "2_2") (pintype "passive"))
      (node (ref "U6") (pin "19") (pinfunction "HVOUT4_19") (pintype "output"))
    )
    (net (code "70") (name "Net-(U6-HVOUT5)") (class "Default")
      (node (ref "R21") (pin "2") (pinfunction "2_2") (pintype "passive"))
      (node (ref "U6") (pin "18") (pinfunction "HVOUT5_18") (pintype "output"))
    )
    (net (code "71") (name "Net-(U6-HVOUT6)") (class "Default")
      (node (ref "T4") (pin "K0") (pinfunction "K0_K0") (pintype "input"))
      (node (ref "T4") (pin "K0_1") (pinfunction "K0_K0_1") (pintype "input"))
      (node (ref "U6") (pin "17") (pinfunction "HVOUT6_17") (pintype "output"))
    )
    (net (code "72") (name "Net-(U6-HVOUT7)") (class "Default")
      (node (ref "T4") (pin "K9") (pinfunction "K9_K9") (pintype "input"))
      (node (ref "T4") (pin "K9_1") (pinfunction "K9_K9_1") (pintype "input"))
      (node (ref "U6") (pin "16") (pinfunction "HVOUT7_16") (pintype "output"))
    )
    (net (code "73") (name "Net-(U6-HVOUT8)") (class "Default")
      (node (ref "T4") (pin "K8") (pinfunction "K8_K8") (pintype "input"))
      (node (ref "T4") (pin "K8_1") (pinfunction "K8_K8_1") (pintype "input"))
      (node (ref "U6") (pin "15") (pinfunction "HVOUT8_15") (pintype "output"))
    )
    (net (code "74") (name "Net-(U6-HVOUT9)") (class "Default")
      (node (ref "T4") (pin "K7") (pinfunction "K7_K7") (pintype "input"))
      (node (ref "T4") (pin "K7_1") (pinfunction "K7_K7_1") (pintype "input"))
      (node (ref "U6") (pin "14") (pinfunction "HVOUT9_14") (pintype "output"))
    )
    (net (code "75") (name "Net-(U6-HVOUT10)") (class "Default")
      (node (ref "T4") (pin "K6") (pinfunction "K6_K6") (pintype "input"))
      (node (ref "T4") (pin "K6_1") (pinfunction "K6_K6_1") (pintype "input"))
      (node (ref "U6") (pin "13") (pinfunction "HVOUT10_13") (pintype "output"))
    )
    (net (code "76") (name "Net-(U6-HVOUT11)") (class "Default")
      (node (ref "T4") (pin "K5") (pinfunction "K5_K5") (pintype "input"))
      (node (ref "T4") (pin "K5_1") (pinfunction "K5_K5_1") (pintype "input"))
      (node (ref "U6") (pin "12") (pinfunction "HVOUT11_12") (pintype "output"))
    )
    (net (code "77") (name "Net-(U6-HVOUT12)") (class "Default")
      (node (ref "T4") (pin "K4") (pinfunction "K4_K4") (pintype "input"))
      (node (ref "T4") (pin "K4_1") (pinfunction "K4_K4_1") (pintype "input"))
      (node (ref "U6") (pin "11") (pinfunction "HVOUT12_11") (pintype "output"))
    )
    (net (code "78") (name "Net-(U6-HVOUT13)") (class "Default")
      (node (ref "T4") (pin "K3") (pinfunction "K3_K3") (pintype "input"))
      (node (ref "T4") (pin "K3_1") (pinfunction "K3_K3_1") (pintype "input"))
      (node (ref "U6") (pin "10") (pinfunction "HVOUT13_10") (pintype "output"))
    )
    (net (code "79") (name "Net-(U6-HVOUT14)") (class "Default")
      (node (ref "T4") (pin "K2") (pinfunction "K2_K2") (pintype "input"))
      (node (ref "T4") (pin "K2_1") (pinfunction "K2_K2_1") (pintype "input"))
      (node (ref "U6") (pin "9") (pinfunction "HVOUT14_9") (pintype "output"))
    )
    (net (code "80") (name "Net-(U6-HVOUT15)") (class "Default")
      (node (ref "T4") (pin "K1") (pinfunction "K1_K1") (pintype "input"))
      (node (ref "T4") (pin "K1_1") (pinfunction "K1_K1_1") (pintype "input"))
      (node (ref "U6") (pin "8") (pinfunction "HVOUT15_8") (pintype "output"))
    )
    (net (code "81") (name "Net-(U6-HVOUT16)") (class "Default")
      (node (ref "R22") (pin "2") (pinfunction "2_2") (pintype "passive"))
      (node (ref "U6") (pin "7") (pinfunction "HVOUT16_7") (pintype "output"))
    )
    (net (code "82") (name "Net-(U6-HVOUT17)") (class "Default")
      (node (ref "R23") (pin "2") (pinfunction "2_2") (pintype "passive"))
      (node (ref "U6") (pin "6") (pinfunction "HVOUT17_6") (pintype "output"))
    )
    (net (code "83") (name "Net-(U6-HVOUT18)") (class "Default")
      (node (ref "T3") (pin "K0") (pinfunction "K0_K0") (pintype "input"))
      (node (ref "T3") (pin "K0_1") (pinfunction "K0_K0_1") (pintype "input"))
      (node (ref "U6") (pin "5") (pinfunction "HVOUT18_5") (pintype "output"))
    )
    (net (code "84") (name "Net-(U6-HVOUT19)") (class "Default")
      (node (ref "T3") (pin "K9") (pinfunction "K9_K9") (pintype "input"))
      (node (ref "T3") (pin "K9_1") (pinfunction "K9_K9_1") (pintype "input"))
      (node (ref "U6") (pin "4") (pinfunction "HVOUT19_4") (pintype "output"))
    )
    (net (code "85") (name "Net-(U6-HVOUT20)") (class "Default")
      (node (ref "T3") (pin "K8") (pinfunction "K8_K8") (pintype "input"))
      (node (ref "T3") (pin "K8_1") (pinfunction "K8_K8_1") (pintype "input"))
      (node (ref "U6") (pin "3") (pinfunction "HVOUT20_3") (pintype "output"))
    )
    (net (code "86") (name "Net-(U6-HVOUT21)") (class "Default")
      (node (ref "T3") (pin "K7") (pinfunction "K7_K7") (pintype "input"))
      (node (ref "T3") (pin "K7_1") (pinfunction "K7_K7_1") (pintype "input"))
      (node (ref "U6") (pin "2") (pinfunction "HVOUT21_2") (pintype "output"))
    )
    (net (code "87") (name "Net-(U6-HVOUT22)") (class "Default")
      (node (ref "T3") (pin "K6") (pinfunction "K6_K6") (pintype "input"))
      (node (ref "T3") (pin "K6_1") (pinfunction "K6_K6_1") (pintype "input"))
      (node (ref "U6") (pin "1") (pinfunction "HVOUT22_1") (pintype "output"))
    )
    (net (code "88") (name "Net-(U6-HVOUT23)") (class "Default")
      (node (ref "T3") (pin "K5") (pinfunction "K5_K5") (pintype "input"))
      (node (ref "T3") (pin "K5_1") (pinfunction "K5_K5_1") (pintype "input"))
      (node (ref "U6") (pin "44") (pinfunction "HVOUT23_44") (pintype "output"))
    )
    (net (code "89") (name "Net-(U6-HVOUT24)") (class "Default")
      (node (ref "T3") (pin "K4") (pinfunction "K4_K4") (pintype "input"))
      (node (ref "T3") (pin "K4_1") (pinfunction "K4_K4_1") (pintype "input"))
      (node (ref "U6") (pin "43") (pinfunction "HVOUT24_43") (pintype "output"))
    )
    (net (code "90") (name "Net-(U6-HVOUT25)") (class "Default")
      (node (ref "T3") (pin "K3") (pinfunction "K3_K3") (pintype "input"))
      (node (ref "T3") (pin "K3_1") (pinfunction "K3_K3_1") (pintype "input"))
      (node (ref "U6") (pin "42") (pinfunction "HVOUT25_42") (pintype "output"))
    )
    (net (code "91") (name "Net-(U6-HVOUT26)") (class "Default")
      (node (ref "T3") (pin "K2") (pinfunction "K2_K2") (pintype "input"))
      (node (ref "T3") (pin "K2_1") (pinfunction "K2_K2_1") (pintype "input"))
      (node (ref "U6") (pin "41") (pinfunction "HVOUT26_41") (pintype "output"))
    )
    (net (code "92") (name "Net-(U6-HVOUT27)") (class "Default")
      (node (ref "T3") (pin "K1") (pinfunction "K1_K1") (pintype "input"))
      (node (ref "T3") (pin "K1_1") (pinfunction "K1_K1_1") (pintype "input"))
      (node (ref "U6") (pin "40") (pinfunction "HVOUT27_40") (pintype "output"))
    )
    (net (code "93") (name "Net-(U6-HVOUT28)") (class "Default")
      (node (ref "R24") (pin "2") (pinfunction "2_2") (pintype "passive"))
      (node (ref "U6") (pin "39") (pinfunction "HVOUT28_39") (pintype "output"))
    )
    (net (code "94") (name "Net-(U6-HVOUT29)") (class "Default")
      (node (ref "R25") (pin "2") (pinfunction "2_2") (pintype "passive"))
      (node (ref "U6") (pin "38") (pinfunction "HVOUT29_38") (pintype "output"))
    )
    (net (code "95") (name "Net-(U6-HVOUT30)") (class "Default")
      (node (ref "T2") (pin "K0") (pinfunction "K0_K0") (pintype "input"))
      (node (ref "T2") (pin "K0_1") (pinfunction "K0_K0_1") (pintype "input"))
      (node (ref "U6") (pin "37") (pinfunction "HVOUT30_37") (pintype "output"))
    )
    (net (code "96") (name "Net-(U6-HVOUT31)") (class "Default")
      (node (ref "T2") (pin "K9") (pinfunction "K9_K9") (pintype "input"))
      (node (ref "T2") (pin "K9_1") (pinfunction "K9_K9_1") (pintype "input"))
      (node (ref "U6") (pin "36") (pinfunction "HVOUT31_36") (pintype "output"))
    )
    (net (code "97") (name "Net-(U6-HVOUT32)") (class "Default")
      (node (ref "T2") (pin "K8") (pinfunction "K8_K8") (pintype "input"))
      (node (ref "T2") (pin "K8_1") (pinfunction "K8_K8_1") (pintype "input"))
      (node (ref "U6") (pin "35") (pinfunction "HVOUT32_35") (pintype "output"))
    )
    (net (code "98") (name "Net-(U7-HVOUT1)") (class "Default")
      (node (ref "T2") (pin "K7") (pinfunction "K7_K7") (pintype "input"))
      (node (ref "T2") (pin "K7_1") (pinfunction "K7_K7_1") (pintype "input"))
      (node (ref "U7") (pin "22") (pinfunction "HVOUT1_22") (pintype "output"))
    )
    (net (code "99") (name "Net-(U7-HVOUT2)") (class "Default")
      (node (ref "T2") (pin "K6") (pinfunction "K6_K6") (pintype "input"))
      (node (ref "T2") (pin "K6_1") (pinfunction "K6_K6_1") (pintype "input"))
      (node (ref "U7") (pin "21") (pinfunction "HVOUT2_21") (pintype "output"))
    )
    (net (code "100") (name "Net-(U7-HVOUT3)") (class "Default")
      (node (ref "T2") (pin "K5") (pinfunction "K5_K5") (pintype "input"))
      (node (ref "T2") (pin "K5_1") (pinfunction "K5_K5_1") (pintype "input"))
      (node (ref "U7") (pin "20") (pinfunction "HVOUT3_20") (pintype "output"))
    )
    (net (code "101") (name "Net-(U7-HVOUT4)") (class "Default")
      (node (ref "T2") (pin "K4") (pinfunction "K4_K4") (pintype "input"))
      (node (ref "T2") (pin "K4_1") (pinfunction "K4_K4_1") (pintype "input"))
      (node (ref "U7") (pin "19") (pinfunction "HVOUT4_19") (pintype "output"))
    )
    (net (code "102") (name "Net-(U7-HVOUT5)") (class "Default")
      (node (ref "T2") (pin "K3") (pinfunction "K3_K3") (pintype "input"))
      (node (ref "T2") (pin "K3_1") (pinfunction "K3_K3_1") (pintype "input"))
      (node (ref "U7") (pin "18") (pinfunction "HVOUT5_18") (pintype "output"))
    )
    (net (code "103") (name "Net-(U7-HVOUT6)") (class "Default")
      (node (ref "T2") (pin "K2") (pinfunction "K2_K2") (pintype "input"))
      (node (ref "T2") (pin "K2_1") (pinfunction "K2_K2_1") (pintype "input"))
      (node (ref "U7") (pin "17") (pinfunction "HVOUT6_17") (pintype "output"))
    )
    (net (code "104") (name "Net-(U7-HVOUT7)") (class "Default")
      (node (ref "T2") (pin "K1") (pinfunction "K1_K1") (pintype "input"))
      (node (ref "T2") (pin "K1_1") (pinfunction "K1_K1_1") (pintype "input"))
      (node (ref "U7") (pin "16") (pinfunction "HVOUT7_16") (pintype "output"))
    )
    (net (code "105") (name "Net-(U7-HVOUT8)") (class "Default")
      (node (ref "R26") (pin "2") (pinfunction "2_2") (pintype "passive"))
      (node (ref "U7") (pin "15") (pinfunction "HVOUT8_15") (pintype "output"))
    )
    (net (code "106") (name "Net-(U7-HVOUT9)") (class "Default")
      (node (ref "R27") (pin "2") (pinfunction "2_2") (pintype "passive"))
      (node (ref "U7") (pin "14") (pinfunction "HVOUT9_14") (pintype "output"))
    )
    (net (code "107") (name "Net-(U7-HVOUT10)") (class "Default")
      (node (ref "T1") (pin "K0") (pinfunction "K0_K0") (pintype "input"))
      (node (ref "T1") (pin "K0_1") (pinfunction "K0_K0_1") (pintype "input"))
      (node (ref "U7") (pin "13") (pinfunction "HVOUT10_13") (pintype "output"))
    )
    (net (code "108") (name "Net-(U7-HVOUT11)") (class "Default")
      (node (ref "T1") (pin "K9") (pinfunction "K9_K9") (pintype "input"))
      (node (ref "T1") (pin "K9_1") (pinfunction "K9_K9_1") (pintype "input"))
      (node (ref "U7") (pin "12") (pinfunction "HVOUT11_12") (pintype "output"))
    )
    (net (code "109") (name "Net-(U7-HVOUT12)") (class "Default")
      (node (ref "T1") (pin "K8") (pinfunction "K8_K8") (pintype "input"))
      (node (ref "T1") (pin "K8_1") (pinfunction "K8_K8_1") (pintype "input"))
      (node (ref "U7") (pin "11") (pinfunction "HVOUT12_11") (pintype "output"))
    )
    (net (code "110") (name "Net-(U7-HVOUT13)") (class "Default")
      (node (ref "T1") (pin "K7") (pinfunction "K7_K7") (pintype "input"))
      (node (ref "T1") (pin "K7_1") (pinfunction "K7_K7_1") (pintype "input"))
      (node (ref "U7") (pin "10") (pinfunction "HVOUT13_10") (pintype "output"))
    )
    (net (code "111") (name "Net-(U7-HVOUT14)") (class "Default")
      (node (ref "T1") (pin "K6") (pinfunction "K6_K6") (pintype "input"))
      (node (ref "T1") (pin "K6_1") (pinfunction "K6_K6_1") (pintype "input"))
      (node (ref "U7") (pin "9") (pinfunction "HVOUT14_9") (pintype "output"))
    )
    (net (code "112") (name "Net-(U7-HVOUT15)") (class "Default")
      (node (ref "T1") (pin "K5") (pinfunction "K5_K5") (pintype "input"))
      (node (ref "T1") (pin "K5_1") (pinfunction "K5_K5_1") (pintype "input"))
      (node (ref "U7") (pin "8") (pinfunction "HVOUT15_8") (pintype "output"))
    )
    (net (code "113") (name "Net-(U7-HVOUT16)") (class "Default")
      (node (ref "T1") (pin "K4") (pinfunction "K4_K4") (pintype "input"))
      (node (ref "T1") (pin "K4_1") (pinfunction "K4_K4_1") (pintype "input"))
      (node (ref "U7") (pin "7") (pinfunction "HVOUT16_7") (pintype "output"))
    )
    (net (code "114") (name "Net-(U7-HVOUT17)") (class "Default")
      (node (ref "T1") (pin "K3") (pinfunction "K3_K3") (pintype "input"))
      (node (ref "T1") (pin "K3_1") (pinfunction "K3_K3_1") (pintype "input"))
      (node (ref "U7") (pin "6") (pinfunction "HVOUT17_6") (pintype "output"))
    )
    (net (code "115") (name "Net-(U7-HVOUT18)") (class "Default")
      (node (ref "T1") (pin "K2") (pinfunction "K2_K2") (pintype "input"))
      (node (ref "T1") (pin "K2_1") (pinfunction "K2_K2_1") (pintype "input"))
      (node (ref "U7") (pin "5") (pinfunction "HVOUT18_5") (pintype "output"))
    )
    (net (code "116") (name "Net-(U7-HVOUT19)") (class "Default")
      (node (ref "T1") (pin "K1") (pinfunction "K1_K1") (pintype "input"))
      (node (ref "T1") (pin "K1_1") (pinfunction "K1_K1_1") (pintype "input"))
      (node (ref "U7") (pin "4") (pinfunction "HVOUT19_4") (pintype "output"))
    )
    (net (code "117") (name "Net-(U7-HVOUT20)") (class "Default")
      (node (ref "R28") (pin "2") (pinfunction "2_2") (pintype "passive"))
      (node (ref "U7") (pin "3") (pinfunction "HVOUT20_3") (pintype "output"))
    )
    (net (code "118") (name "Net-(U7-HVOUT21)") (class "Default")
      (node (ref "R29") (pin "2") (pinfunction "2_2") (pintype "passive"))
      (node (ref "U7") (pin "2") (pinfunction "HVOUT21_2") (pintype "output"))
    )
    (net (code "119") (name "Net-(U7-HVOUT22)") (class "Default")
      (node (ref "T0") (pin "K0") (pinfunction "K0_K0") (pintype "input"))
      (node (ref "T0") (pin "K0_1") (pinfunction "K0_K0_1") (pintype "input"))
      (node (ref "U7") (pin "1") (pinfunction "HVOUT22_1") (pintype "output"))
    )
    (net (code "120") (name "Net-(U7-HVOUT23)") (class "Default")
      (node (ref "T0") (pin "K9") (pinfunction "K9_K9") (pintype "input"))
      (node (ref "T0") (pin "K9_1") (pinfunction "K9_K9_1") (pintype "input"))
      (node (ref "U7") (pin "44") (pinfunction "HVOUT23_44") (pintype "output"))
    )
    (net (code "121") (name "Net-(U7-HVOUT24)") (class "Default")
      (node (ref "T0") (pin "K8") (pinfunction "K8_K8") (pintype "input"))
      (node (ref "T0") (pin "K8_1") (pinfunction "K8_K8_1") (pintype "input"))
      (node (ref "U7") (pin "43") (pinfunction "HVOUT24_43") (pintype "output"))
    )
    (net (code "122") (name "Net-(U7-HVOUT25)") (class "Default")
      (node (ref "T0") (pin "K7") (pinfunction "K7_K7") (pintype "input"))
      (node (ref "T0") (pin "K7_1") (pinfunction "K7_K7_1") (pintype "input"))
      (node (ref "U7") (pin "42") (pinfunction "HVOUT25_42") (pintype "output"))
    )
    (net (code "123") (name "Net-(U7-HVOUT26)") (class "Default")
      (node (ref "T0") (pin "K6") (pinfunction "K6_K6") (pintype "input"))
      (node (ref "T0") (pin "K6_1") (pinfunction "K6_K6_1") (pintype "input"))
      (node (ref "U7") (pin "41") (pinfunction "HVOUT26_41") (pintype "output"))
    )
    (net (code "124") (name "Net-(U7-HVOUT27)") (class "Default")
      (node (ref "T0") (pin "K5") (pinfunction "K5_K5") (pintype "input"))
      (node (ref "T0") (pin "K5_1") (pinfunction "K5_K5_1") (pintype "input"))
      (node (ref "U7") (pin "40") (pinfunction "HVOUT27_40") (pintype "output"))
    )
    (net (code "125") (name "Net-(U7-HVOUT28)") (class "Default")
      (node (ref "T0") (pin "K4") (pinfunction "K4_K4") (pintype "input"))
      (node (ref "T0") (pin "K4_1") (pinfunction "K4_K4_1") (pintype "input"))
      (node (ref "U7") (pin "39") (pinfunction "HVOUT28_39") (pintype "output"))
    )
    (net (code "126") (name "Net-(U7-HVOUT29)") (class "Default")
      (node (ref "T0") (pin "K3") (pinfunction "K3_K3") (pintype "input"))
      (node (ref "T0") (pin "K3_1") (pinfunction "K3_K3_1") (pintype "input"))
      (node (ref "U7") (pin "38") (pinfunction "HVOUT29_38") (pintype "output"))
    )
    (net (code "127") (name "Net-(U7-HVOUT30)") (class "Default")
      (node (ref "T0") (pin "K2") (pinfunction "K2_K2") (pintype "input"))
      (node (ref "T0") (pin "K2_1") (pinfunction "K2_K2_1") (pintype "input"))
      (node (ref "U7") (pin "37") (pinfunction "HVOUT30_37") (pintype "output"))
    )
    (net (code "128") (name "Net-(U7-HVOUT31)") (class "Default")
      (node (ref "T0") (pin "K1") (pinfunction "K1_K1") (pintype "input"))
      (node (ref "T0") (pin "K1_1") (pinfunction "K1_K1_1") (pintype "input"))
      (node (ref "U7") (pin "36") (pinfunction "HVOUT31_36") (pintype "output"))
    )
    (net (code "129") (name "Net-(U7-HVOUT32)") (class "Default")
      (node (ref "R30") (pin "2") (pinfunction "2_2") (pintype "passive"))
      (node (ref "U7") (pin "35") (pinfunction "HVOUT32_35") (pintype "output"))
    )
    (net (code "130") (name "unconnected-(NC5-Pad1)") (class "Default")
      (node (ref "NC5") (pin "1") (pinfunction "1_1") (pintype "passive"))
    )
    (net (code "131") (name "unconnected-(NC5-Pad2)") (class "Default")
      (node (ref "NC5") (pin "2") (pinfunction "2_2") (pintype "passive"))
    )
    (net (code "132") (name "unconnected-(NC6-Pad1)") (class "Default")
      (node (ref "NC6") (pin "1") (pinfunction "1_1") (pintype "passive"))
    )
    (net (code "133") (name "unconnected-(NC6-Pad2)") (class "Default")
      (node (ref "NC6") (pin "2") (pinfunction "2_2") (pintype "passive"))
    )
    (net (code "134") (name "unconnected-(NC7-Pad1)") (class "Default")
      (node (ref "NC7") (pin "1") (pinfunction "1_1") (pintype "passive"))
    )
    (net (code "135") (name "unconnected-(NC7-Pad2)") (class "Default")
      (node (ref "NC7") (pin "2") (pinfunction "2_2") (pintype "passive"))
    )
    (net (code "136") (name "unconnected-(NC8-Pad1)") (class "Default")
      (node (ref "NC8") (pin "1") (pinfunction "1_1") (pintype "passive"))
    )
    (net (code "137") (name "unconnected-(U5-NC-Pad34)") (class "Default")
      (node (ref "U5") (pin "34") (pinfunction "NC_34") (pintype "no_connect"))
    )
    (net (code "138") (name "unconnected-(U5-NC_2-Pad24)") (class "Default")
      (node (ref "U5") (pin "24") (pinfunction "NC_2_24") (pintype "no_connect"))
    )
    (net (code "139") (name "unconnected-(U5-NC_3-Pad25)") (class "Default")
      (node (ref "U5") (pin "25") (pinfunction "NC_3_25") (pintype "no_connect"))
    )
    (net (code "140") (name "unconnected-(U5-NC_4-Pad26)") (class "Default")
      (node (ref "U5") (pin "26") (pinfunction "NC_4_26") (pintype "no_connect"))
    )
    (net (code "141") (name "unconnected-(U6-NC-Pad34)") (class "Default")
      (node (ref "U6") (pin "34") (pinfunction "NC_34") (pintype "no_connect"))
    )
    (net (code "142") (name "unconnected-(U6-NC_2-Pad24)") (class "Default")
      (node (ref "U6") (pin "24") (pinfunction "NC_2_24") (pintype "no_connect"))
    )
    (net (code "143") (name "unconnected-(U6-NC_3-Pad25)") (class "Default")
      (node (ref "U6") (pin "25") (pinfunction "NC_3_25") (pintype "no_connect"))
    )
    (net (code "144") (name "unconnected-(U6-NC_4-Pad26)") (class "Default")
      (node (ref "U6") (pin "26") (pinfunction "NC_4_26") (pintype "no_connect"))
    )
    (net (code "145") (name "unconnected-(U7-DATAOUT-Pad23)") (class "Default")
      (node (ref "U7") (pin "23") (pinfunction "DATAOUT_23") (pintype "output"))
    )
    (net (code "146") (name "unconnected-(U7-NC-Pad34)") (class "Default")
      (node (ref "U7") (pin "34") (pinfunction "NC_34") (pintype "no_connect"))
    )
    (net (code "147") (name "unconnected-(U7-NC_2-Pad24)") (class "Default")
      (node (ref "U7") (pin "24") (pinfunction "NC_2_24") (pintype "no_connect"))
    )
    (net (code "148") (name "unconnected-(U7-NC_3-Pad25)") (class "Default")
      (node (ref "U7") (pin "25") (pinfunction "NC_3_25") (pintype "no_connect"))
    )
    (net (code "149") (name "unconnected-(U7-NC_4-Pad26)") (class "Default")
      (node (ref "U7") (pin "26") (pinfunction "NC_4_26") (pintype "no_connect"))
    )
  )
)
